# UFO.net
KiCad netlist of a schematic drawn in EAGLE
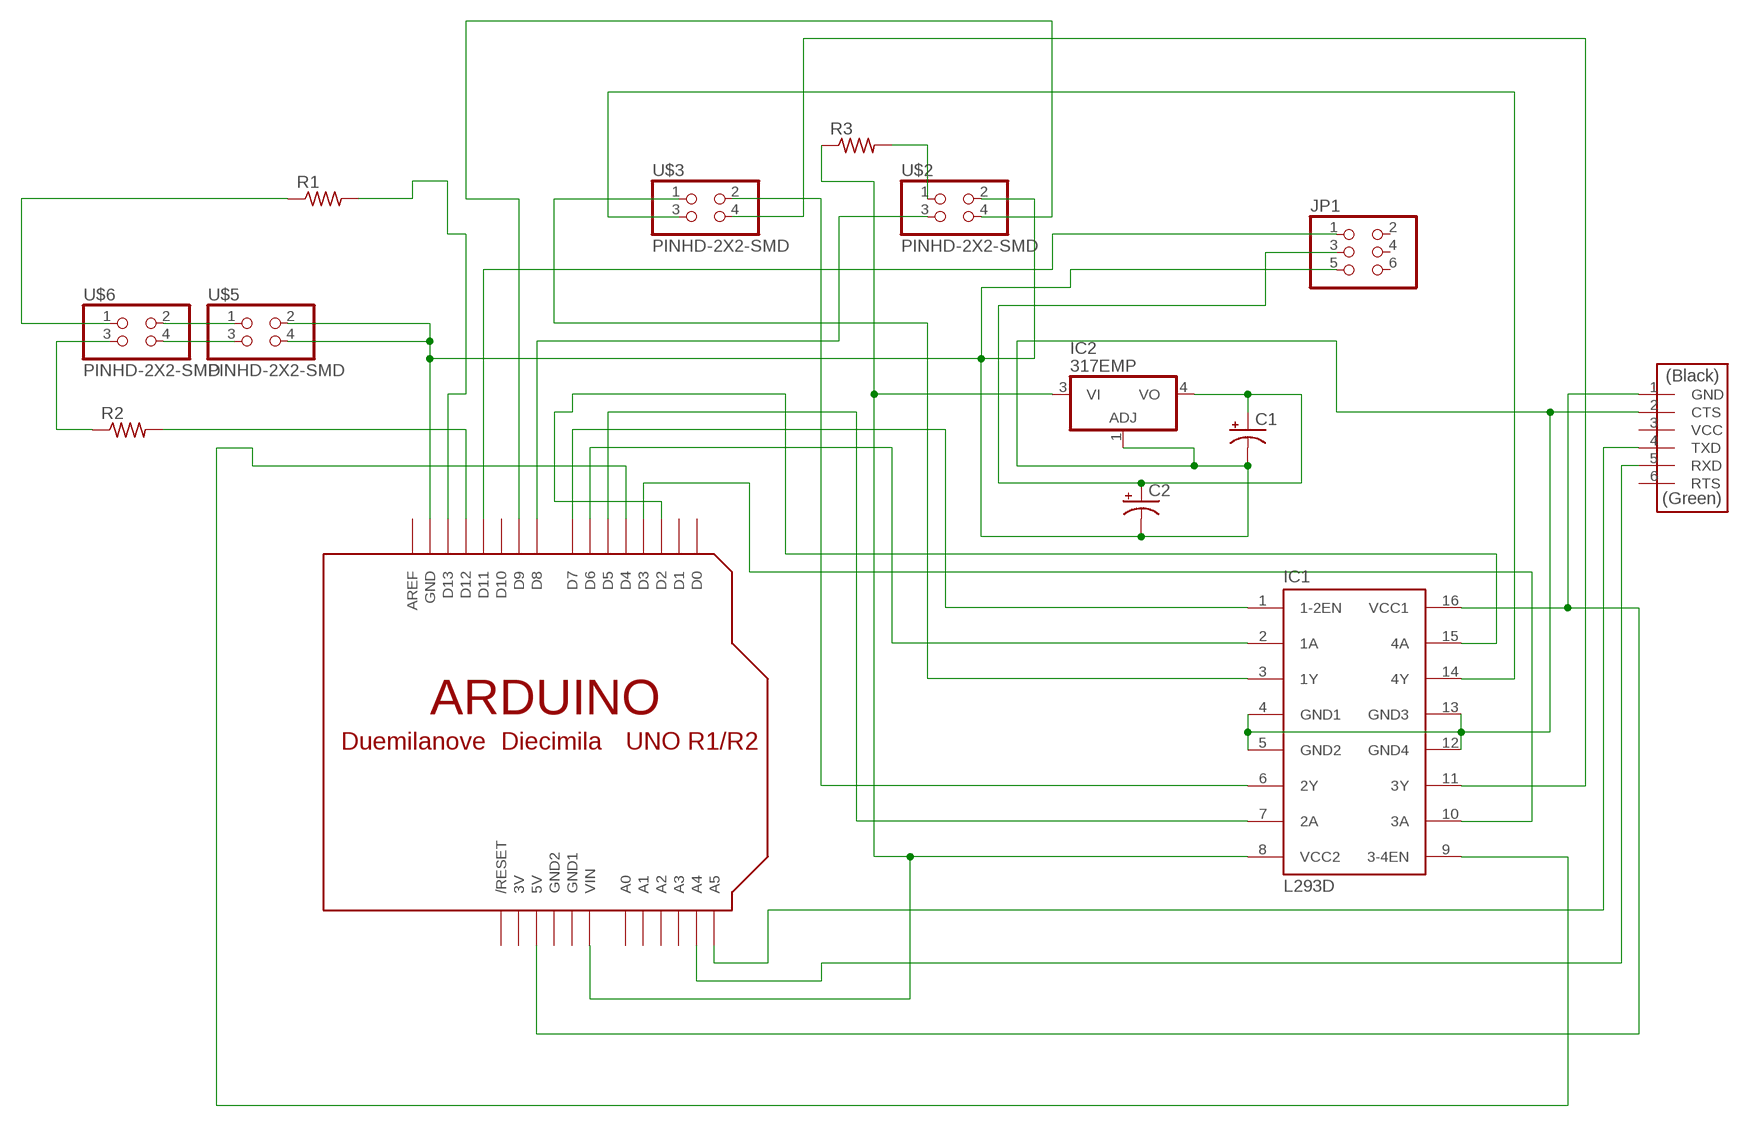
[diagram p0: schematic, sheet 1]

(export (version "E")
  (design (tool "Eeschema 10.0.6"))
  (components
    (comp (ref "C1")
      (value "CPOL-USE/7260-38W")
      (footprint "eagle-import:E_7260-38W")
      (libsource (lib "eagle-import") (part "CPOL-USE/7260-38W"))
    )
    (comp (ref "C2")
      (value "CPOL-USE/7260-38W")
      (footprint "eagle-import:E_7260-38W")
      (libsource (lib "eagle-import") (part "CPOL-USE/7260-38W"))
    )
    (comp (ref "IC1")
      (value "L293D")
      (footprint "eagle-import:DIL16")
      (libsource (lib "eagle-import") (part "L293D"))
    )
    (comp (ref "IC2")
      (value "317EMP")
      (footprint "eagle-import:SOT223")
      (libsource (lib "eagle-import") (part "317EMP"))
    )
    (comp (ref "JP1")
      (value "PINHD-2X3-SMD")
      (footprint "eagle-import:2X03SMD")
      (libsource (lib "eagle-import") (part "PINHD-2X3-SMD"))
    )
    (comp (ref "R1")
      (value "RES-US1206")
      (footprint "eagle-import:R1206")
      (libsource (lib "eagle-import") (part "RES-US1206"))
    )
    (comp (ref "R2")
      (value "RES-US1206")
      (footprint "eagle-import:R1206")
      (libsource (lib "eagle-import") (part "RES-US1206"))
    )
    (comp (ref "R3")
      (value "RES-US1206FAB")
      (footprint "eagle-import:R1206FAB")
      (libsource (lib "eagle-import") (part "RES-US1206FAB"))
    )
    (comp (ref "U$1")
      (value "ARDUINO-NOHOLE")
      (footprint "eagle-import:ARDUINO-NOHOLE")
      (libsource (lib "eagle-import") (part "ARDUINO-NOHOLE"))
    )
    (comp (ref "U$2")
      (value "PINHD-2X2-SMD")
      (footprint "eagle-import:2X02SMD")
      (libsource (lib "eagle-import") (part "PINHD-2X2-SMD"))
    )
    (comp (ref "U$3")
      (value "PINHD-2X2-SMD")
      (footprint "eagle-import:2X02SMD")
      (libsource (lib "eagle-import") (part "PINHD-2X2-SMD"))
    )
    (comp (ref "U$4")
      (value "FTDI-SMD-HEADER")
      (footprint "eagle-import:1X06SMD")
      (libsource (lib "eagle-import") (part "FTDI-SMD-HEADER"))
    )
    (comp (ref "U$5")
      (value "PINHD-2X2-SMD")
      (footprint "eagle-import:2X02SMD")
      (libsource (lib "eagle-import") (part "PINHD-2X2-SMD"))
    )
    (comp (ref "U$6")
      (value "PINHD-2X2-SMD")
      (footprint "eagle-import:2X02SMD")
      (libsource (lib "eagle-import") (part "PINHD-2X2-SMD"))
    )
  )
  (nets
    (net (code "1") (name "/3V") (class "Default")
      (node (ref "U$1") (pin "3V") (pinfunction "3V_3V") (pintype "power_in"))
    )
    (net (code "2") (name "/GND1") (class "Default")
      (node (ref "U$1") (pin "GND1") (pinfunction "GND1_GND1") (pintype "power_in"))
    )
    (net (code "3") (name "/GND2") (class "Default")
      (node (ref "U$1") (pin "GND2") (pinfunction "GND2_GND2") (pintype "power_in"))
    )
    (net (code "4") (name "Net-(IC1-1-2EN)") (class "Default")
      (node (ref "IC1") (pin "1") (pinfunction "1-2EN_1") (pintype "input"))
      (node (ref "U$1") (pin "D7") (pinfunction "D7_D7") (pintype "bidirectional"))
    )
    (net (code "5") (name "Net-(IC1-1A)") (class "Default")
      (node (ref "IC1") (pin "2") (pinfunction "1A_2") (pintype "input"))
      (node (ref "U$1") (pin "D6") (pinfunction "D6_D6") (pintype "bidirectional"))
    )
    (net (code "6") (name "Net-(IC1-1Y)") (class "Default")
      (node (ref "IC1") (pin "3") (pinfunction "1Y_3") (pintype "output"))
      (node (ref "U$3") (pin "1") (pinfunction "1_1") (pintype "passive"))
    )
    (net (code "7") (name "Net-(IC1-2A)") (class "Default")
      (node (ref "IC1") (pin "7") (pinfunction "2A_7") (pintype "input"))
      (node (ref "U$1") (pin "D5") (pinfunction "D5_D5") (pintype "bidirectional"))
    )
    (net (code "8") (name "Net-(IC1-2Y)") (class "Default")
      (node (ref "IC1") (pin "6") (pinfunction "2Y_6") (pintype "output"))
      (node (ref "U$3") (pin "2") (pinfunction "2_2") (pintype "passive"))
    )
    (net (code "9") (name "Net-(IC1-3-4EN)") (class "Default")
      (node (ref "IC1") (pin "9") (pinfunction "3-4EN_9") (pintype "input"))
      (node (ref "U$1") (pin "D4") (pinfunction "D4_D4") (pintype "bidirectional"))
    )
    (net (code "10") (name "Net-(IC1-3A)") (class "Default")
      (node (ref "IC1") (pin "10") (pinfunction "3A_10") (pintype "input"))
      (node (ref "U$1") (pin "D3") (pinfunction "D3_D3") (pintype "bidirectional"))
    )
    (net (code "11") (name "Net-(IC1-3Y)") (class "Default")
      (node (ref "IC1") (pin "11") (pinfunction "3Y_11") (pintype "output"))
      (node (ref "U$3") (pin "4") (pinfunction "4_4") (pintype "passive"))
    )
    (net (code "12") (name "Net-(IC1-4A)") (class "Default")
      (node (ref "IC1") (pin "15") (pinfunction "4A_15") (pintype "input"))
      (node (ref "U$1") (pin "D2") (pinfunction "D2_D2") (pintype "bidirectional"))
    )
    (net (code "13") (name "Net-(IC1-4Y)") (class "Default")
      (node (ref "IC1") (pin "14") (pinfunction "4Y_14") (pintype "output"))
      (node (ref "U$3") (pin "3") (pinfunction "3_3") (pintype "passive"))
    )
    (net (code "14") (name "Net-(IC1-GND1)") (class "Default")
      (node (ref "C1") (pin "-") (pinfunction "-_-") (pintype "passive"))
      (node (ref "C2") (pin "-") (pinfunction "-_-") (pintype "passive"))
      (node (ref "IC1") (pin "12") (pinfunction "GND4_12") (pintype "power_in"))
      (node (ref "IC1") (pin "13") (pinfunction "GND3_13") (pintype "power_in"))
      (node (ref "IC1") (pin "4") (pinfunction "GND1_4") (pintype "power_in"))
      (node (ref "IC1") (pin "5") (pinfunction "GND2_5") (pintype "power_in"))
      (node (ref "IC2") (pin "1") (pinfunction "ADJ_1") (pintype "input"))
      (node (ref "JP1") (pin "5") (pinfunction "5_5") (pintype "passive"))
      (node (ref "U$1") (pin "GND") (pinfunction "GND_GND") (pintype "power_in"))
      (node (ref "U$2") (pin "2") (pinfunction "2_2") (pintype "passive"))
      (node (ref "U$4") (pin "2") (pinfunction "CTS_2") (pintype "bidirectional"))
      (node (ref "U$5") (pin "2") (pinfunction "2_2") (pintype "passive"))
      (node (ref "U$5") (pin "4") (pinfunction "4_4") (pintype "passive"))
    )
    (net (code "15") (name "Net-(IC1-VCC1)") (class "Default")
      (node (ref "IC1") (pin "16") (pinfunction "VCC1_16") (pintype "power_in"))
      (node (ref "U$1") (pin "5V") (pinfunction "5V_5V") (pintype "power_in"))
      (node (ref "U$4") (pin "1") (pinfunction "GND_1") (pintype "bidirectional"))
    )
    (net (code "16") (name "Net-(IC1-VCC2)") (class "Default")
      (node (ref "IC1") (pin "8") (pinfunction "VCC2_8") (pintype "power_in"))
      (node (ref "IC2") (pin "3") (pinfunction "VI_3") (pintype "input"))
      (node (ref "R3") (pin "1") (pinfunction "1_1") (pintype "passive"))
      (node (ref "U$1") (pin "VIN") (pinfunction "VIN_VIN") (pintype "power_in"))
    )
    (net (code "17") (name "Net-(IC2-VO)") (class "Default")
      (node (ref "C1") (pin "+") (pinfunction "+_+") (pintype "passive"))
      (node (ref "C2") (pin "+") (pinfunction "+_+") (pintype "passive"))
      (node (ref "IC2") (pin "4") (pinfunction "VO_4") (pintype "passive"))
      (node (ref "JP1") (pin "3") (pinfunction "3_3") (pintype "passive"))
    )
    (net (code "18") (name "Net-(JP1-Pad1)") (class "Default")
      (node (ref "JP1") (pin "1") (pinfunction "1_1") (pintype "passive"))
      (node (ref "U$1") (pin "D11") (pinfunction "D11_D11") (pintype "bidirectional"))
    )
    (net (code "19") (name "Net-(R1-Pad1)") (class "Default")
      (node (ref "R1") (pin "1") (pinfunction "1_1") (pintype "passive"))
      (node (ref "U$6") (pin "1") (pinfunction "1_1") (pintype "passive"))
    )
    (net (code "20") (name "Net-(R1-Pad2)") (class "Default")
      (node (ref "R1") (pin "2") (pinfunction "2_2") (pintype "passive"))
      (node (ref "U$1") (pin "D13") (pinfunction "D13_D13") (pintype "bidirectional"))
    )
    (net (code "21") (name "Net-(R2-Pad1)") (class "Default")
      (node (ref "R2") (pin "1") (pinfunction "1_1") (pintype "passive"))
      (node (ref "U$6") (pin "3") (pinfunction "3_3") (pintype "passive"))
    )
    (net (code "22") (name "Net-(R2-Pad2)") (class "Default")
      (node (ref "R2") (pin "2") (pinfunction "2_2") (pintype "passive"))
      (node (ref "U$1") (pin "D12") (pinfunction "D12_D12") (pintype "bidirectional"))
    )
    (net (code "23") (name "Net-(R3-Pad2)") (class "Default")
      (node (ref "R3") (pin "2") (pinfunction "2_2") (pintype "passive"))
      (node (ref "U$2") (pin "1") (pinfunction "1_1") (pintype "passive"))
    )
    (net (code "24") (name "Net-(U$1-PadD8)") (class "Default")
      (node (ref "U$1") (pin "D8") (pinfunction "D8_D8") (pintype "bidirectional"))
      (node (ref "U$2") (pin "3") (pinfunction "3_3") (pintype "passive"))
    )
    (net (code "25") (name "Net-(U$1-PadD9)") (class "Default")
      (node (ref "U$1") (pin "D9") (pinfunction "D9_D9") (pintype "bidirectional"))
      (node (ref "U$2") (pin "4") (pinfunction "4_4") (pintype "passive"))
    )
    (net (code "26") (name "Net-(U$4-RXD)") (class "Default")
      (node (ref "U$1") (pin "A4") (pinfunction "A4_A4") (pintype "bidirectional"))
      (node (ref "U$4") (pin "5") (pinfunction "RXD_5") (pintype "bidirectional"))
    )
    (net (code "27") (name "Net-(U$4-TXD)") (class "Default")
      (node (ref "U$1") (pin "A5") (pinfunction "A5_A5") (pintype "bidirectional"))
      (node (ref "U$4") (pin "4") (pinfunction "TXD_4") (pintype "bidirectional"))
    )
    (net (code "28") (name "Net-(U$5-Pad1)") (class "Default")
      (node (ref "U$5") (pin "1") (pinfunction "1_1") (pintype "passive"))
      (node (ref "U$6") (pin "2") (pinfunction "2_2") (pintype "passive"))
    )
    (net (code "29") (name "Net-(U$5-Pad3)") (class "Default")
      (node (ref "U$5") (pin "3") (pinfunction "3_3") (pintype "passive"))
      (node (ref "U$6") (pin "4") (pinfunction "4_4") (pintype "passive"))
    )
    (net (code "30") (name "unconnected-(JP1-Pad2)") (class "Default")
      (node (ref "JP1") (pin "2") (pinfunction "2_2") (pintype "passive"))
    )
    (net (code "31") (name "unconnected-(JP1-Pad4)") (class "Default")
      (node (ref "JP1") (pin "4") (pinfunction "4_4") (pintype "passive"))
    )
    (net (code "32") (name "unconnected-(JP1-Pad6)") (class "Default")
      (node (ref "JP1") (pin "6") (pinfunction "6_6") (pintype "passive"))
    )
    (net (code "33") (name "unconnected-(U$1-PadA0)") (class "Default")
      (node (ref "U$1") (pin "A0") (pinfunction "A0_A0") (pintype "bidirectional"))
    )
    (net (code "34") (name "unconnected-(U$1-PadA1)") (class "Default")
      (node (ref "U$1") (pin "A1") (pinfunction "A1_A1") (pintype "bidirectional"))
    )
    (net (code "35") (name "unconnected-(U$1-PadA2)") (class "Default")
      (node (ref "U$1") (pin "A2") (pinfunction "A2_A2") (pintype "bidirectional"))
    )
    (net (code "36") (name "unconnected-(U$1-PadA3)") (class "Default")
      (node (ref "U$1") (pin "A3") (pinfunction "A3_A3") (pintype "bidirectional"))
    )
    (net (code "37") (name "unconnected-(U$1-PadAREF)") (class "Default")
      (node (ref "U$1") (pin "AREF") (pinfunction "AREF_AREF") (pintype "bidirectional"))
    )
    (net (code "38") (name "unconnected-(U$1-PadD0)") (class "Default")
      (node (ref "U$1") (pin "D0") (pinfunction "D0_D0") (pintype "bidirectional"))
    )
    (net (code "39") (name "unconnected-(U$1-PadD1)") (class "Default")
      (node (ref "U$1") (pin "D1") (pinfunction "D1_D1") (pintype "bidirectional"))
    )
    (net (code "40") (name "unconnected-(U$1-PadD10)") (class "Default")
      (node (ref "U$1") (pin "D10") (pinfunction "D10_D10") (pintype "bidirectional"))
    )
    (net (code "41") (name "unconnected-(U$1-{slash}RESET-PadRESET)") (class "Default")
      (node (ref "U$1") (pin "RESET") (pinfunction "/RESET_RESET") (pintype "bidirectional"))
    )
    (net (code "42") (name "unconnected-(U$4-RTS-Pad6)") (class "Default")
      (node (ref "U$4") (pin "6") (pinfunction "RTS_6") (pintype "bidirectional"))
    )
    (net (code "43") (name "unconnected-(U$4-VCC-Pad3)") (class "Default")
      (node (ref "U$4") (pin "3") (pinfunction "VCC_3") (pintype "bidirectional"))
    )
  )
)
